# Overview.net
KiCad netlist of a schematic drawn in Altium Designer
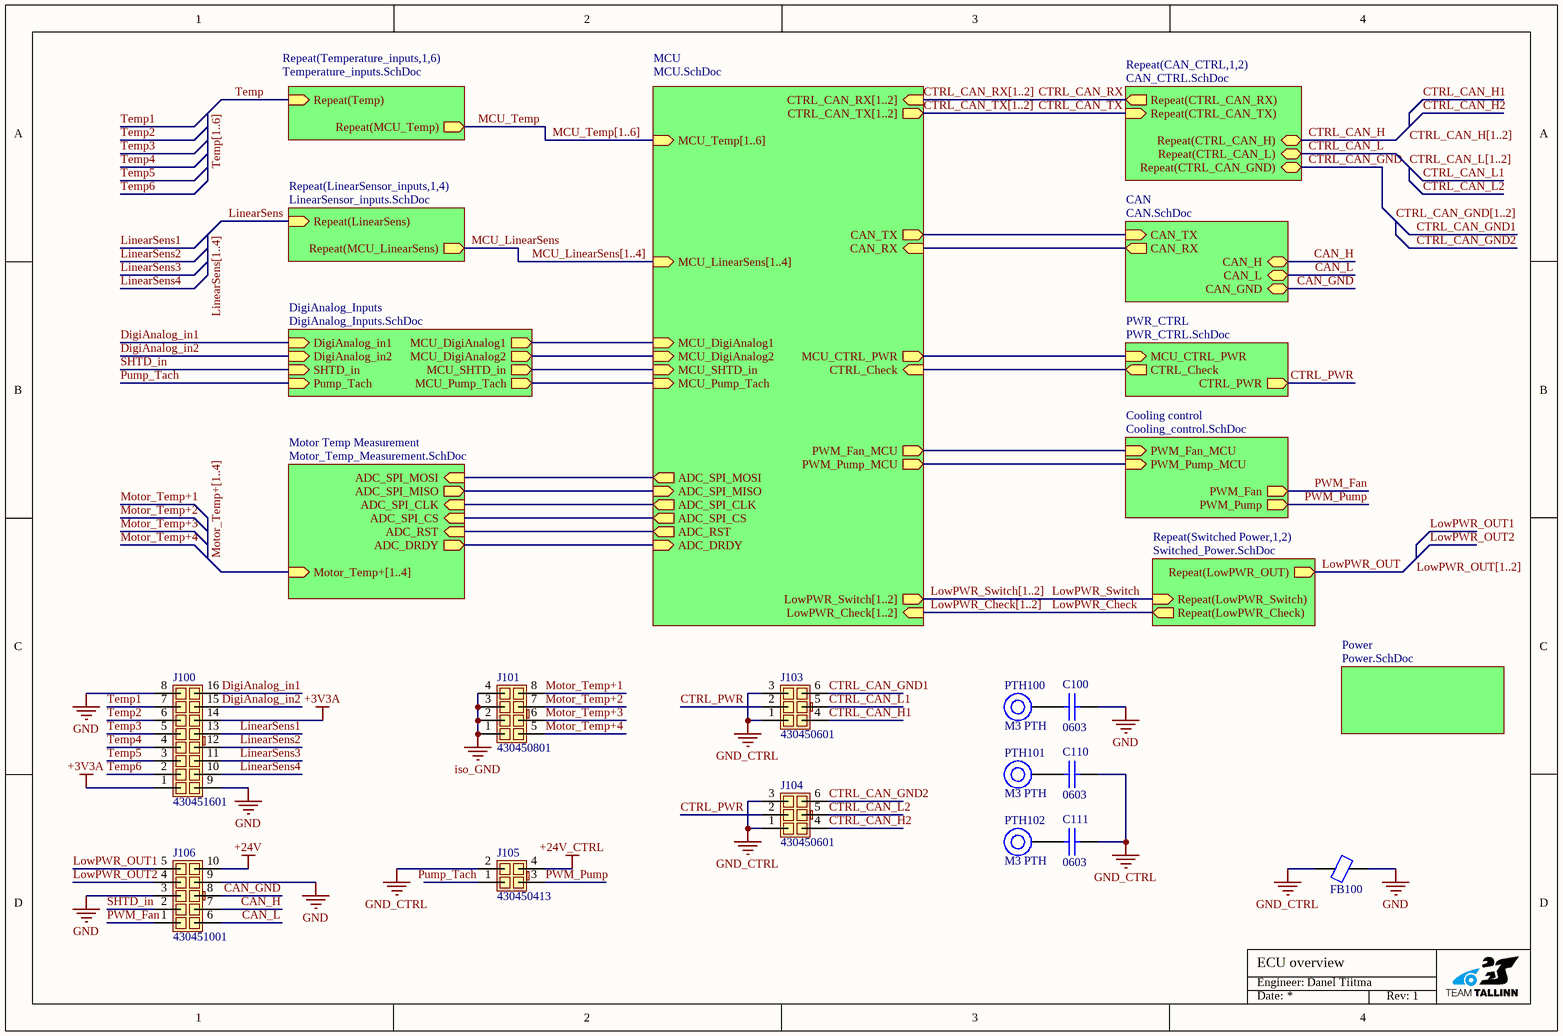
[diagram p0: Overview.SchDoc]

(export (version "E")
  (design (tool "Eeschema 10.0.6"))
  (components
    (comp (ref "C100")
      (value "0603")
      (footprint "CAP [0603] 1608")
      (description "Default capacitor part")
      (libsource (lib "Formula Student Team Tallinn (Estonia)") (part "Capacitor"))
    )
    (comp (ref "C110")
      (value "0603")
      (footprint "CAP [0603] 1608")
      (description "Default capacitor part")
      (libsource (lib "Formula Student Team Tallinn (Estonia)") (part "Capacitor"))
    )
    (comp (ref "C111")
      (value "0603")
      (footprint "CAP [0603] 1608")
      (description "Default capacitor part")
      (libsource (lib "Formula Student Team Tallinn (Estonia)") (part "Capacitor"))
    )
    (comp (ref "FB100")
      (value "742792653")
      (footprint "IND [0603] 1608")
      (description "Ferrite Chip, 1 Function(s), 0.5A, 2 Pin(s)")
      (fields (field (name "MANUFACTURER") "WURTH ELEKTRONIK"))
      (libsource (lib "Formula Student Team Tallinn (Estonia)") (part "Ferrite Bead"))
    )
    (comp (ref "J100")
      (value "430451601")
      (footprint "430451601")
      (description "Rectangular Power Connector, 16 Contact(s), Male, Solder Terminal, Receptacle")
      (fields (field (name "MANUFACTURER") "Molex") (field (name "MANUFACTURER PART NUMBER") "43045-1601"))
      (libsource (lib "Formula Student Team Tallinn (Estonia)") (part "Connector Micro-Fit 2x8"))
    )
    (comp (ref "J101")
      (value "430450801")
      (footprint "430450801")
      (description "Rectangular Power Connector, 8 Contact(s), Male, Solder Terminal, Receptacle")
      (fields (field (name "MANUFACTURER") "Molex") (field (name "MANUFACTURER PART NUMBER") "43045-0801"))
      (libsource (lib "Formula Student Team Tallinn (Estonia)") (part "Connector Micro-Fit 2x4"))
    )
    (comp (ref "J103")
      (value "430450601")
      (footprint "430450601")
      (description "Rectangular Power Connector, 6 Contact(s), Male, Solder Terminal, Receptacle")
      (fields (field (name "MANUFACTURER") "Molex") (field (name "MANUFACTURER PART NUMBER") "43045-0601"))
      (libsource (lib "Formula Student Team Tallinn (Estonia)") (part "Connector Micro-Fit 2x3"))
    )
    (comp (ref "J104")
      (value "430450601")
      (footprint "430450601")
      (description "Rectangular Power Connector, 6 Contact(s), Male, Solder Terminal, Receptacle")
      (fields (field (name "MANUFACTURER") "Molex") (field (name "MANUFACTURER PART NUMBER") "43045-0601"))
      (libsource (lib "Formula Student Team Tallinn (Estonia)") (part "Connector Micro-Fit 2x3"))
    )
    (comp (ref "J105")
      (value "430450413")
      (footprint "430450413")
      (description "Rectangular Power Connector, 4 Contact(s), Male, Solder Terminal, Receptacle")
      (fields (field (name "MANUFACTURER PART NUMBER") "43045-0413") (field (name "MANUFACTURER") "Molex"))
      (libsource (lib "Formula Student Team Tallinn (Estonia)") (part "Connector Micro-Fit 2x2"))
    )
    (comp (ref "J106")
      (value "430451001")
      (footprint "430451001")
      (description "Rectangular Power Connector, 10 Contact(s), Male, Solder Terminal, Receptacle")
      (fields (field (name "MANUFACTURER") "Molex"))
      (libsource (lib "Formula Student Team Tallinn (Estonia)") (part "Connector Micro-Fit 2x5"))
    )
    (comp (ref "PTH100")
      (value "M3 PTH")
      (footprint "M3 PTH")
      (description "M3 plated through hole for mounting")
      (libsource (lib "Formula Student Team Tallinn (Estonia)") (part "PTH"))
    )
    (comp (ref "PTH101")
      (value "M3 PTH")
      (footprint "M3 PTH")
      (description "M3 plated through hole for mounting")
      (libsource (lib "Formula Student Team Tallinn (Estonia)") (part "PTH"))
    )
    (comp (ref "PTH102")
      (value "M3 PTH")
      (footprint "M3 PTH")
      (description "M3 plated through hole for mounting")
      (libsource (lib "Formula Student Team Tallinn (Estonia)") (part "PTH"))
    )
  )
  (nets
    (net (code "19") (name "+3V3A") (class "Default")
      (node (ref "J100") (pin "1") (pinfunction "1_1") (pintype "passive"))
      (node (ref "J100") (pin "14") (pinfunction "14_14") (pintype "passive"))
    )
    (net (code "20") (name "+24V") (class "Default")
      (node (ref "J106") (pin "10") (pinfunction "10_10") (pintype "passive"))
    )
    (net (code "21") (name "+24V_CTRL") (class "Default")
      (node (ref "J105") (pin "4") (pinfunction "4_4") (pintype "passive"))
    )
    (net (code "28") (name "/CAN_GND") (class "Default")
      (node (ref "J106") (pin "8") (pinfunction "8_8") (pintype "passive"))
    )
    (net (code "29") (name "/CAN_H") (class "Default")
      (node (ref "J106") (pin "7") (pinfunction "7_7") (pintype "passive"))
    )
    (net (code "30") (name "/CAN_L") (class "Default")
      (node (ref "J106") (pin "6") (pinfunction "6_6") (pintype "passive"))
    )
    (net (code "34") (name "/CTRL_CAN_GND1") (class "Default")
      (node (ref "J103") (pin "6") (pinfunction "6_6") (pintype "passive"))
    )
    (net (code "35") (name "/CTRL_CAN_GND2") (class "Default")
      (node (ref "J104") (pin "6") (pinfunction "6_6") (pintype "passive"))
    )
    (net (code "38") (name "/CTRL_CAN_H1") (class "Default")
      (node (ref "J103") (pin "4") (pinfunction "4_4") (pintype "passive"))
    )
    (net (code "39") (name "/CTRL_CAN_H2") (class "Default")
      (node (ref "J104") (pin "4") (pinfunction "4_4") (pintype "passive"))
    )
    (net (code "42") (name "/CTRL_CAN_L1") (class "Default")
      (node (ref "J103") (pin "5") (pinfunction "5_5") (pintype "passive"))
    )
    (net (code "43") (name "/CTRL_CAN_L2") (class "Default")
      (node (ref "J104") (pin "5") (pinfunction "5_5") (pintype "passive"))
    )
    (net (code "50") (name "/CTRL_PWR") (class "Default")
      (node (ref "J103") (pin "2") (pinfunction "2_2") (pintype "passive"))
      (node (ref "J104") (pin "2") (pinfunction "2_2") (pintype "passive"))
    )
    (net (code "51") (name "/DigiAnalog_in1") (class "Default")
      (node (ref "J100") (pin "16") (pinfunction "16_16") (pintype "passive"))
    )
    (net (code "52") (name "/DigiAnalog_in2") (class "Default")
      (node (ref "J100") (pin "15") (pinfunction "15_15") (pintype "passive"))
    )
    (net (code "54") (name "/LinearSens1") (class "Default")
      (node (ref "J100") (pin "13") (pinfunction "13_13") (pintype "passive"))
    )
    (net (code "55") (name "/LinearSens2") (class "Default")
      (node (ref "J100") (pin "12") (pinfunction "12_12") (pintype "passive"))
    )
    (net (code "56") (name "/LinearSens3") (class "Default")
      (node (ref "J100") (pin "11") (pinfunction "11_11") (pintype "passive"))
    )
    (net (code "57") (name "/LinearSens4") (class "Default")
      (node (ref "J100") (pin "10") (pinfunction "6_10") (pintype "passive"))
    )
    (net (code "62") (name "/LowPWR_OUT1") (class "Default")
      (node (ref "J106") (pin "5") (pinfunction "5_5") (pintype "passive"))
    )
    (net (code "63") (name "/LowPWR_OUT2") (class "Default")
      (node (ref "J106") (pin "4") (pinfunction "4_4") (pintype "passive"))
    )
    (net (code "76") (name "/Motor_Temp+1") (class "Default")
      (node (ref "J101") (pin "8") (pinfunction "8_8") (pintype "passive"))
    )
    (net (code "77") (name "/Motor_Temp+2") (class "Default")
      (node (ref "J101") (pin "7") (pinfunction "7_7") (pintype "passive"))
    )
    (net (code "78") (name "/Motor_Temp+3") (class "Default")
      (node (ref "J101") (pin "6") (pinfunction "6_6") (pintype "passive"))
    )
    (net (code "79") (name "/Motor_Temp+4") (class "Default")
      (node (ref "J101") (pin "5") (pinfunction "5_5") (pintype "passive"))
    )
    (net (code "81") (name "/PWM_Fan") (class "Default")
      (node (ref "J106") (pin "1") (pinfunction "1_1") (pintype "passive"))
    )
    (net (code "83") (name "/PWM_Pump") (class "Default")
      (node (ref "J105") (pin "3") (pinfunction "3_3") (pintype "passive"))
    )
    (net (code "85") (name "/Pump_Tach") (class "Default")
      (node (ref "J105") (pin "1") (pinfunction "1_1") (pintype "passive"))
    )
    (net (code "86") (name "/SHTD_in") (class "Default")
      (node (ref "J106") (pin "2") (pinfunction "2_2") (pintype "passive"))
    )
    (net (code "88") (name "/Temp1") (class "Default")
      (node (ref "J100") (pin "7") (pinfunction "7_7") (pintype "passive"))
    )
    (net (code "89") (name "/Temp2") (class "Default")
      (node (ref "J100") (pin "6") (pinfunction "6_6") (pintype "passive"))
    )
    (net (code "90") (name "/Temp3") (class "Default")
      (node (ref "J100") (pin "5") (pinfunction "5_5") (pintype "passive"))
    )
    (net (code "91") (name "/Temp4") (class "Default")
      (node (ref "J100") (pin "4") (pinfunction "4_4") (pintype "passive"))
    )
    (net (code "92") (name "/Temp5") (class "Default")
      (node (ref "J100") (pin "3") (pinfunction "3_3") (pintype "passive"))
    )
    (net (code "93") (name "/Temp6") (class "Default")
      (node (ref "J100") (pin "2") (pinfunction "2_2") (pintype "passive"))
    )
    (net (code "95") (name "GND") (class "Default")
      (node (ref "C100") (pin "1") (pinfunction "1_1") (pintype "passive"))
      (node (ref "FB100") (pin "2") (pinfunction "2_2") (pintype "passive"))
      (node (ref "J100") (pin "8") (pinfunction "8_8") (pintype "passive"))
      (node (ref "J100") (pin "9") (pinfunction "9_9") (pintype "passive"))
      (node (ref "J106") (pin "3") (pinfunction "3_3") (pintype "passive"))
      (node (ref "J106") (pin "9") (pinfunction "9_9") (pintype "passive"))
    )
    (net (code "96") (name "GND_CTRL") (class "Default")
      (node (ref "C110") (pin "2") (pinfunction "2_2") (pintype "passive"))
      (node (ref "C111") (pin "2") (pinfunction "2_2") (pintype "passive"))
      (node (ref "FB100") (pin "1") (pinfunction "1_1") (pintype "passive"))
      (node (ref "J103") (pin "1") (pinfunction "1_1") (pintype "passive"))
      (node (ref "J103") (pin "3") (pinfunction "3_3") (pintype "passive"))
      (node (ref "J104") (pin "1") (pinfunction "1_1") (pintype "passive"))
      (node (ref "J104") (pin "3") (pinfunction "3_3") (pintype "passive"))
      (node (ref "J105") (pin "2") (pinfunction "2_2") (pintype "passive"))
    )
    (net (code "97") (name "Net-(C100-Pad2)") (class "Default")
      (node (ref "C100") (pin "2") (pinfunction "2_2") (pintype "passive"))
      (node (ref "PTH100") (pin "1") (pinfunction "1_1") (pintype "passive"))
    )
    (net (code "98") (name "Net-(C110-Pad1)") (class "Default")
      (node (ref "C110") (pin "1") (pinfunction "1_1") (pintype "passive"))
      (node (ref "PTH101") (pin "1") (pinfunction "1_1") (pintype "passive"))
    )
    (net (code "99") (name "Net-(C111-Pad1)") (class "Default")
      (node (ref "C111") (pin "1") (pinfunction "1_1") (pintype "passive"))
      (node (ref "PTH102") (pin "1") (pinfunction "1_1") (pintype "passive"))
    )
    (net (code "100") (name "iso_GND") (class "Default")
      (node (ref "J101") (pin "1") (pinfunction "1_1") (pintype "passive"))
      (node (ref "J101") (pin "2") (pinfunction "2_2") (pintype "passive"))
      (node (ref "J101") (pin "3") (pinfunction "3_3") (pintype "passive"))
      (node (ref "J101") (pin "4") (pinfunction "4_4") (pintype "passive"))
    )
  )
)
